# Slave_Micro.net
KiCad netlist of a schematic drawn in Altium Designer
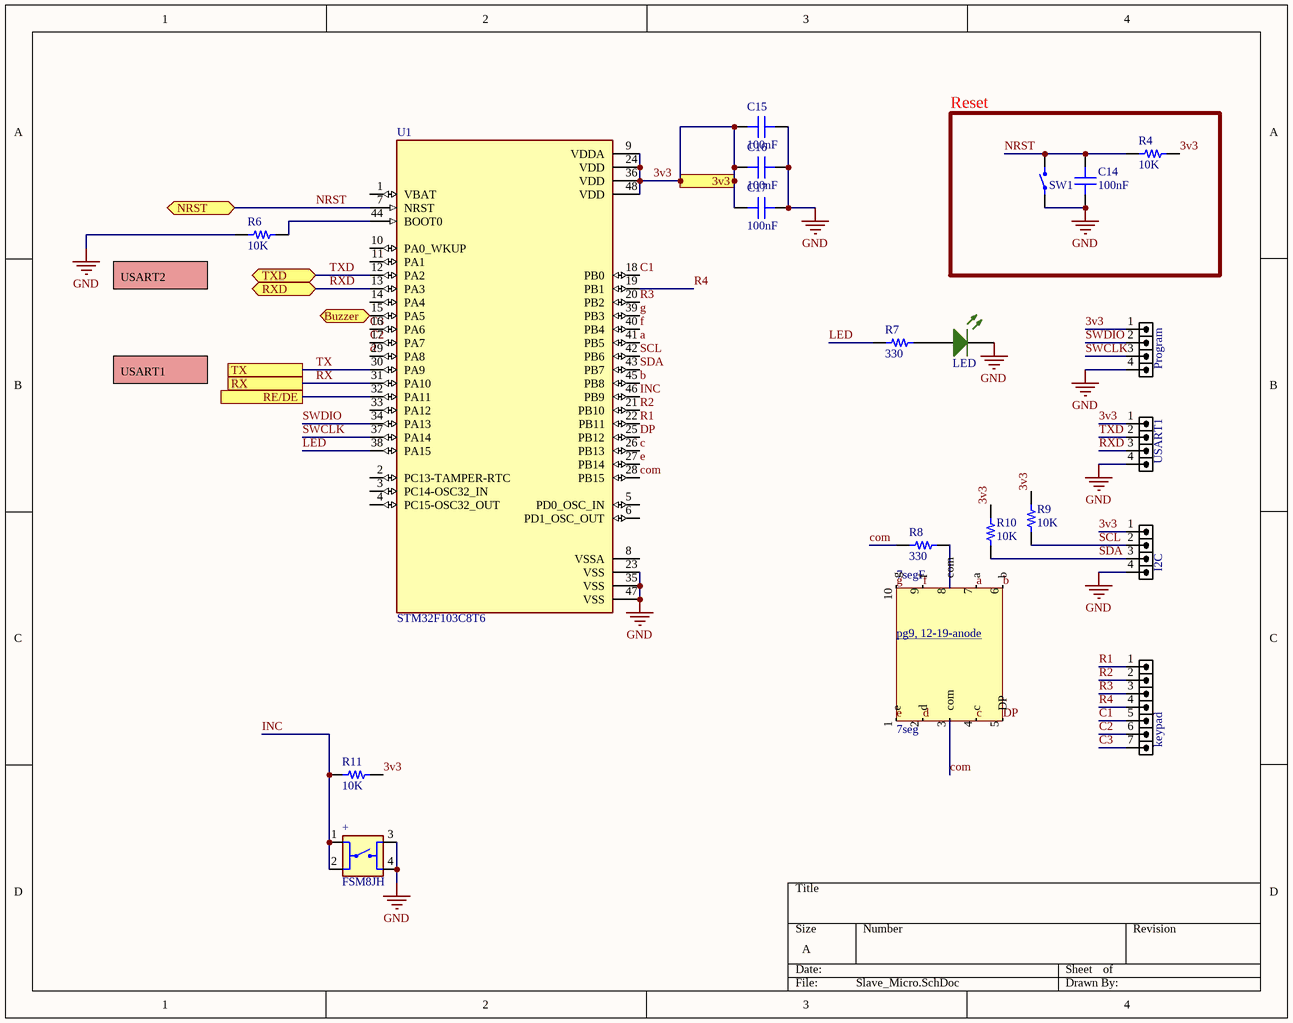
[diagram p0: Slave_Micro.SchDoc]

(export (version "E")
  (design (tool "Eeschema 10.0.6"))
  (components
    (comp (ref "+")
      (value "FSM8JH")
      (footprint "SW_FSM8JH")
      (description "Tactile Switch SPST-NO Top Actuated Through Hole")
      (fields (field (name "MF") "TE Connectivity"))
      (libsource (lib "FSM8JH") (part "FSM8JH"))
    )
    (comp (ref "7seg")
      (value "7seg")
      (footprint "PCBComponent_1")
      (description "file:///C:/Users/Tamana/Downloads/7SEG-12-19mm-GREEN-ANOD.pdf")
      (libsource (lib "7seg") (part "7seg"))
    )
    (comp (ref "C14")
      (value "100nF")
      (footprint "CAP 0805_2012")
      (description "SMT Capacitor")
      (libsource (lib "Capacitor") (part "Cap 0805"))
    )
    (comp (ref "C15")
      (value "100nF")
      (footprint "CAP 0805_2012")
      (description "SMT Capacitor")
      (libsource (lib "Capacitor") (part "Cap 0805"))
    )
    (comp (ref "C16")
      (value "100nF")
      (footprint "CAP 0805_2012")
      (description "SMT Capacitor")
      (libsource (lib "Capacitor") (part "Cap 0805"))
    )
    (comp (ref "C17")
      (value "100nF")
      (footprint "CAP 0805_2012")
      (description "SMT Capacitor")
      (libsource (lib "Capacitor") (part "Cap 0805"))
    )
    (comp (ref "I2C")
      (value "HDR1X4")
      (footprint "HDR_1X4")
      (description "CONN, HEADER, Male, pitch: 2.54mm, 4POS")
      (libsource (lib "Conn Header") (part "HDR_1X4"))
    )
    (comp (ref "keypad")
      (value "HDR1X7")
      (footprint "HDR_1X7")
      (description "CONN, HEADER, Male, pitch: 2.54mm, 7POS")
      (libsource (lib "Conn Header") (part "HDR_1X7"))
    )
    (comp (ref "LED")
      (value "LED SMD 0805 GREEN")
      (footprint "LED_0805_GREEN")
      (libsource (lib "Led") (part "LED SMD 0805 GREEN"))
    )
    (comp (ref "Program")
      (value "HDR1X4")
      (footprint "HDR_1X4")
      (description "CONN, HEADER, Male, pitch: 2.54mm, 4POS")
      (libsource (lib "Conn Header") (part "HDR_1X4"))
    )
    (comp (ref "R4")
      (value "10K")
      (footprint "RES 0805_2012")
      (description "SMT Resistor")
      (libsource (lib "Resistor") (part "Res 0805"))
    )
    (comp (ref "R6")
      (value "10K")
      (footprint "RES 0805_2012")
      (description "SMT Resistor")
      (libsource (lib "Resistor") (part "Res 0805"))
    )
    (comp (ref "R7")
      (value "330")
      (footprint "RES 0805_2012")
      (description "SMT Resistor")
      (libsource (lib "Resistor") (part "Res 0805"))
    )
    (comp (ref "R8")
      (value "330")
      (footprint "RES 0805_2012")
      (description "SMT Resistor")
      (libsource (lib "Resistor") (part "Res 0805"))
    )
    (comp (ref "R9")
      (value "10K")
      (footprint "RES 0805_2012")
      (description "SMT Resistor")
      (libsource (lib "Resistor") (part "Res 0805"))
    )
    (comp (ref "R10")
      (value "10K")
      (footprint "RES 0805_2012")
      (description "SMT Resistor")
      (libsource (lib "Resistor") (part "Res 0805"))
    )
    (comp (ref "R11")
      (value "10K")
      (footprint "RES 0805_2012")
      (description "SMT Resistor")
      (libsource (lib "Resistor") (part "Res 0805"))
    )
    (comp (ref "SW1")
      (value "Tactile 2PIN 6X3.5mm H4.57mm (SMD)")
      (footprint "SWPBS_SPST_6X3X5")
      (description "Tactile Switch SPST-NO Top Actuated Surface Mount")
      (fields (field (name "PARTNUMBER") "FSMSMTR-ND"))
      (libsource (lib "Switch") (part "Tactile 2PIN 6X3.5mm H4.57mm (SMD)"))
    )
    (comp (ref "U1")
      (value "STM32F103C8T6")
      (footprint "QFP50P900X900X160-48N")
      (description "ARM® Cortex®-M3 STM32F1 Microcontroller IC 32-Bit 72MHz 64KB (64K x 8) FLASH 48-LQFP (7x7)")
      (fields (field (name "MF") "STMicroelectronics"))
      (libsource (lib "STM32F103C8T6") (part "STM32F103C8T6"))
    )
    (comp (ref "USART1")
      (value "HDR1X4")
      (footprint "HDR_1X4")
      (description "CONN, HEADER, Male, pitch: 2.54mm, 4POS")
      (libsource (lib "Conn Header") (part "HDR_1X4"))
    )
  )
  (nets
    (net (code "1") (name "/3v3") (class "Default")
      (node (ref "C15") (pin "2") (pinfunction "2_2") (pintype "passive"))
      (node (ref "C16") (pin "2") (pinfunction "2_2") (pintype "passive"))
      (node (ref "C17") (pin "2") (pinfunction "2_2") (pintype "passive"))
      (node (ref "I2C") (pin "1") (pinfunction "1_1") (pintype "passive"))
      (node (ref "Program") (pin "1") (pinfunction "1_1") (pintype "passive"))
      (node (ref "R10") (pin "2") (pinfunction "2_2") (pintype "passive"))
      (node (ref "R11") (pin "2") (pinfunction "2_2") (pintype "passive"))
      (node (ref "R4") (pin "2") (pinfunction "2_2") (pintype "passive"))
      (node (ref "R9") (pin "2") (pinfunction "2_2") (pintype "passive"))
      (node (ref "U1") (pin "24") (pinfunction "VDD_24") (pintype "power_in"))
      (node (ref "U1") (pin "36") (pinfunction "VDD_36") (pintype "power_in"))
      (node (ref "U1") (pin "48") (pinfunction "VDD_48") (pintype "power_in"))
      (node (ref "U1") (pin "9") (pinfunction "VDDA_9") (pintype "power_in"))
      (node (ref "USART1") (pin "1") (pinfunction "1_1") (pintype "passive"))
    )
    (net (code "2") (name "/Buzzer") (class "Default")
      (node (ref "U1") (pin "15") (pinfunction "PA5_15") (pintype "bidirectional"))
    )
    (net (code "3") (name "/C1") (class "Default")
      (node (ref "U1") (pin "18") (pinfunction "PB0_18") (pintype "bidirectional"))
      (node (ref "keypad") (pin "5") (pinfunction "5_5") (pintype "passive"))
    )
    (net (code "4") (name "/C2") (class "Default")
      (node (ref "U1") (pin "17") (pinfunction "PA7_17") (pintype "bidirectional"))
      (node (ref "keypad") (pin "6") (pinfunction "6_6") (pintype "passive"))
    )
    (net (code "5") (name "/C3") (class "Default")
      (node (ref "U1") (pin "16") (pinfunction "PA6_16") (pintype "bidirectional"))
      (node (ref "keypad") (pin "7") (pinfunction "7_7") (pintype "passive"))
    )
    (net (code "6") (name "/DP") (class "Default")
      (node (ref "7seg") (pin "5") (pinfunction "DP_5") (pintype "passive"))
      (node (ref "U1") (pin "25") (pinfunction "PB12_25") (pintype "bidirectional"))
    )
    (net (code "7") (name "/INC") (class "Default")
      (node (ref "+") (pin "1") (pinfunction "1_1") (pintype "passive"))
      (node (ref "+") (pin "2") (pinfunction "2_2") (pintype "passive"))
      (node (ref "R11") (pin "1") (pinfunction "1_1") (pintype "passive"))
      (node (ref "U1") (pin "46") (pinfunction "PB9_46") (pintype "bidirectional"))
    )
    (net (code "8") (name "/LED") (class "Default")
      (node (ref "R7") (pin "1") (pinfunction "1_1") (pintype "passive"))
      (node (ref "U1") (pin "38") (pinfunction "PA15_38") (pintype "bidirectional"))
    )
    (net (code "9") (name "/NRST") (class "Default")
      (node (ref "C14") (pin "2") (pinfunction "2_2") (pintype "passive"))
      (node (ref "R4") (pin "1") (pinfunction "1_1") (pintype "passive"))
      (node (ref "SW1") (pin "2") (pinfunction "2_2") (pintype "passive"))
      (node (ref "U1") (pin "7") (pinfunction "NRST_7") (pintype "input"))
    )
    (net (code "10") (name "/R1") (class "Default")
      (node (ref "U1") (pin "22") (pinfunction "PB11_22") (pintype "bidirectional"))
      (node (ref "keypad") (pin "1") (pinfunction "1_1") (pintype "passive"))
    )
    (net (code "11") (name "/R2") (class "Default")
      (node (ref "U1") (pin "21") (pinfunction "PB10_21") (pintype "bidirectional"))
      (node (ref "keypad") (pin "2") (pinfunction "2_2") (pintype "passive"))
    )
    (net (code "12") (name "/R3") (class "Default")
      (node (ref "U1") (pin "20") (pinfunction "PB2_20") (pintype "bidirectional"))
      (node (ref "keypad") (pin "3") (pinfunction "3_3") (pintype "passive"))
    )
    (net (code "13") (name "/R4") (class "Default")
      (node (ref "U1") (pin "19") (pinfunction "PB1_19") (pintype "bidirectional"))
      (node (ref "keypad") (pin "4") (pinfunction "4_4") (pintype "passive"))
    )
    (net (code "14") (name "/RE{slash}DE") (class "Default")
      (node (ref "U1") (pin "32") (pinfunction "PA11_32") (pintype "bidirectional"))
    )
    (net (code "15") (name "/RX") (class "Default")
      (node (ref "U1") (pin "31") (pinfunction "PA10_31") (pintype "bidirectional"))
    )
    (net (code "16") (name "/RXD") (class "Default")
      (node (ref "U1") (pin "13") (pinfunction "PA3_13") (pintype "bidirectional"))
      (node (ref "USART1") (pin "3") (pinfunction "3_3") (pintype "passive"))
    )
    (net (code "17") (name "/SCL") (class "Default")
      (node (ref "I2C") (pin "2") (pinfunction "2_2") (pintype "passive"))
      (node (ref "R9") (pin "1") (pinfunction "1_1") (pintype "passive"))
      (node (ref "U1") (pin "42") (pinfunction "PB6_42") (pintype "bidirectional"))
    )
    (net (code "18") (name "/SDA") (class "Default")
      (node (ref "I2C") (pin "3") (pinfunction "3_3") (pintype "passive"))
      (node (ref "R10") (pin "1") (pinfunction "1_1") (pintype "passive"))
      (node (ref "U1") (pin "43") (pinfunction "PB7_43") (pintype "bidirectional"))
    )
    (net (code "19") (name "/SWCLK") (class "Default")
      (node (ref "Program") (pin "3") (pinfunction "3_3") (pintype "passive"))
      (node (ref "U1") (pin "37") (pinfunction "PA14_37") (pintype "bidirectional"))
    )
    (net (code "20") (name "/SWDIO") (class "Default")
      (node (ref "Program") (pin "2") (pinfunction "2_2") (pintype "passive"))
      (node (ref "U1") (pin "34") (pinfunction "PA13_34") (pintype "bidirectional"))
    )
    (net (code "21") (name "/TX") (class "Default")
      (node (ref "U1") (pin "30") (pinfunction "PA9_30") (pintype "bidirectional"))
    )
    (net (code "22") (name "/TXD") (class "Default")
      (node (ref "U1") (pin "12") (pinfunction "PA2_12") (pintype "bidirectional"))
      (node (ref "USART1") (pin "2") (pinfunction "2_2") (pintype "passive"))
    )
    (net (code "23") (name "/a") (class "Default")
      (node (ref "7seg") (pin "7") (pinfunction "a_7") (pintype "passive"))
      (node (ref "U1") (pin "41") (pinfunction "PB5_41") (pintype "bidirectional"))
    )
    (net (code "24") (name "/b") (class "Default")
      (node (ref "7seg") (pin "6") (pinfunction "b_6") (pintype "passive"))
      (node (ref "U1") (pin "45") (pinfunction "PB8_45") (pintype "bidirectional"))
    )
    (net (code "25") (name "/c") (class "Default")
      (node (ref "7seg") (pin "4") (pinfunction "c_4") (pintype "passive"))
      (node (ref "U1") (pin "26") (pinfunction "PB13_26") (pintype "bidirectional"))
    )
    (net (code "26") (name "/com") (class "Default")
      (node (ref "7seg") (pin "3") (pinfunction "com_3") (pintype "passive"))
      (node (ref "R8") (pin "1") (pinfunction "1_1") (pintype "passive"))
      (node (ref "U1") (pin "28") (pinfunction "PB15_28") (pintype "bidirectional"))
    )
    (net (code "27") (name "/d") (class "Default")
      (node (ref "7seg") (pin "2") (pinfunction "d_2") (pintype "passive"))
      (node (ref "U1") (pin "29") (pinfunction "PA8_29") (pintype "bidirectional"))
    )
    (net (code "28") (name "/e") (class "Default")
      (node (ref "7seg") (pin "1") (pinfunction "e_1") (pintype "passive"))
      (node (ref "U1") (pin "27") (pinfunction "PB14_27") (pintype "bidirectional"))
    )
    (net (code "29") (name "/f") (class "Default")
      (node (ref "7seg") (pin "9") (pinfunction "f_9") (pintype "passive"))
      (node (ref "U1") (pin "40") (pinfunction "PB4_40") (pintype "bidirectional"))
    )
    (net (code "30") (name "/g") (class "Default")
      (node (ref "7seg") (pin "10") (pinfunction "g_10") (pintype "passive"))
      (node (ref "U1") (pin "39") (pinfunction "PB3_39") (pintype "bidirectional"))
    )
    (net (code "31") (name "GND") (class "Default")
      (node (ref "+") (pin "3") (pinfunction "3_3") (pintype "passive"))
      (node (ref "+") (pin "4") (pinfunction "4_4") (pintype "passive"))
      (node (ref "C14") (pin "1") (pinfunction "1_1") (pintype "passive"))
      (node (ref "C15") (pin "1") (pinfunction "1_1") (pintype "passive"))
      (node (ref "C16") (pin "1") (pinfunction "1_1") (pintype "passive"))
      (node (ref "C17") (pin "1") (pinfunction "1_1") (pintype "passive"))
      (node (ref "I2C") (pin "4") (pinfunction "4_4") (pintype "passive"))
      (node (ref "LED") (pin "2") (pinfunction "K_2") (pintype "passive"))
      (node (ref "Program") (pin "4") (pinfunction "4_4") (pintype "passive"))
      (node (ref "R6") (pin "1") (pinfunction "1_1") (pintype "passive"))
      (node (ref "SW1") (pin "1") (pinfunction "1_1") (pintype "passive"))
      (node (ref "U1") (pin "23") (pinfunction "VSS_23") (pintype "power_in"))
      (node (ref "U1") (pin "35") (pinfunction "VSS_35") (pintype "power_in"))
      (node (ref "U1") (pin "47") (pinfunction "VSS_47") (pintype "power_in"))
      (node (ref "USART1") (pin "4") (pinfunction "4_4") (pintype "passive"))
    )
    (net (code "32") (name "Net-(7segF-com-Pad8)") (class "Default")
      (node (ref "7seg") (pin "8") (pinfunction "com_8") (pintype "passive"))
      (node (ref "R8") (pin "2") (pinfunction "2_2") (pintype "passive"))
    )
    (net (code "33") (name "Net-(LED-A)") (class "Default")
      (node (ref "LED") (pin "1") (pinfunction "A_1") (pintype "passive"))
      (node (ref "R7") (pin "2") (pinfunction "2_2") (pintype "passive"))
    )
    (net (code "34") (name "Net-(U1-BOOT0)") (class "Default")
      (node (ref "R6") (pin "2") (pinfunction "2_2") (pintype "passive"))
      (node (ref "U1") (pin "44") (pinfunction "BOOT0_44") (pintype "input"))
    )
    (net (code "35") (name "unconnected-(U1-PA0_WKUP-Pad10)") (class "Default")
      (node (ref "U1") (pin "10") (pinfunction "PA0_WKUP_10") (pintype "bidirectional"))
    )
    (net (code "36") (name "unconnected-(U1-PA1-Pad11)") (class "Default")
      (node (ref "U1") (pin "11") (pinfunction "PA1_11") (pintype "bidirectional"))
    )
    (net (code "37") (name "unconnected-(U1-PA4-Pad14)") (class "Default")
      (node (ref "U1") (pin "14") (pinfunction "PA4_14") (pintype "bidirectional"))
    )
    (net (code "38") (name "unconnected-(U1-PA12-Pad33)") (class "Default")
      (node (ref "U1") (pin "33") (pinfunction "PA12_33") (pintype "bidirectional"))
    )
    (net (code "39") (name "unconnected-(U1-PC13-TAMPER-RTC-Pad2)") (class "Default")
      (node (ref "U1") (pin "2") (pinfunction "PC13-TAMPER-RTC_2") (pintype "bidirectional"))
    )
    (net (code "40") (name "unconnected-(U1-PC14-OSC32_IN-Pad3)") (class "Default")
      (node (ref "U1") (pin "3") (pinfunction "PC14-OSC32_IN_3") (pintype "bidirectional"))
    )
    (net (code "41") (name "unconnected-(U1-PC15-OSC32_OUT-Pad4)") (class "Default")
      (node (ref "U1") (pin "4") (pinfunction "PC15-OSC32_OUT_4") (pintype "bidirectional"))
    )
    (net (code "42") (name "unconnected-(U1-PD0_OSC_IN-Pad5)") (class "Default")
      (node (ref "U1") (pin "5") (pinfunction "PD0_OSC_IN_5") (pintype "bidirectional"))
    )
    (net (code "43") (name "unconnected-(U1-PD1_OSC_OUT-Pad6)") (class "Default")
      (node (ref "U1") (pin "6") (pinfunction "PD1_OSC_OUT_6") (pintype "bidirectional"))
    )
    (net (code "44") (name "unconnected-(U1-VBAT-Pad1)") (class "Default")
      (node (ref "U1") (pin "1") (pinfunction "VBAT_1") (pintype "bidirectional"))
    )
    (net (code "45") (name "unconnected-(U1-VSSA-Pad8)") (class "Default")
      (node (ref "U1") (pin "8") (pinfunction "VSSA_8") (pintype "power_in"))
    )
  )
)
